# Others.net
KiCad netlist of a schematic drawn in Altium Designer
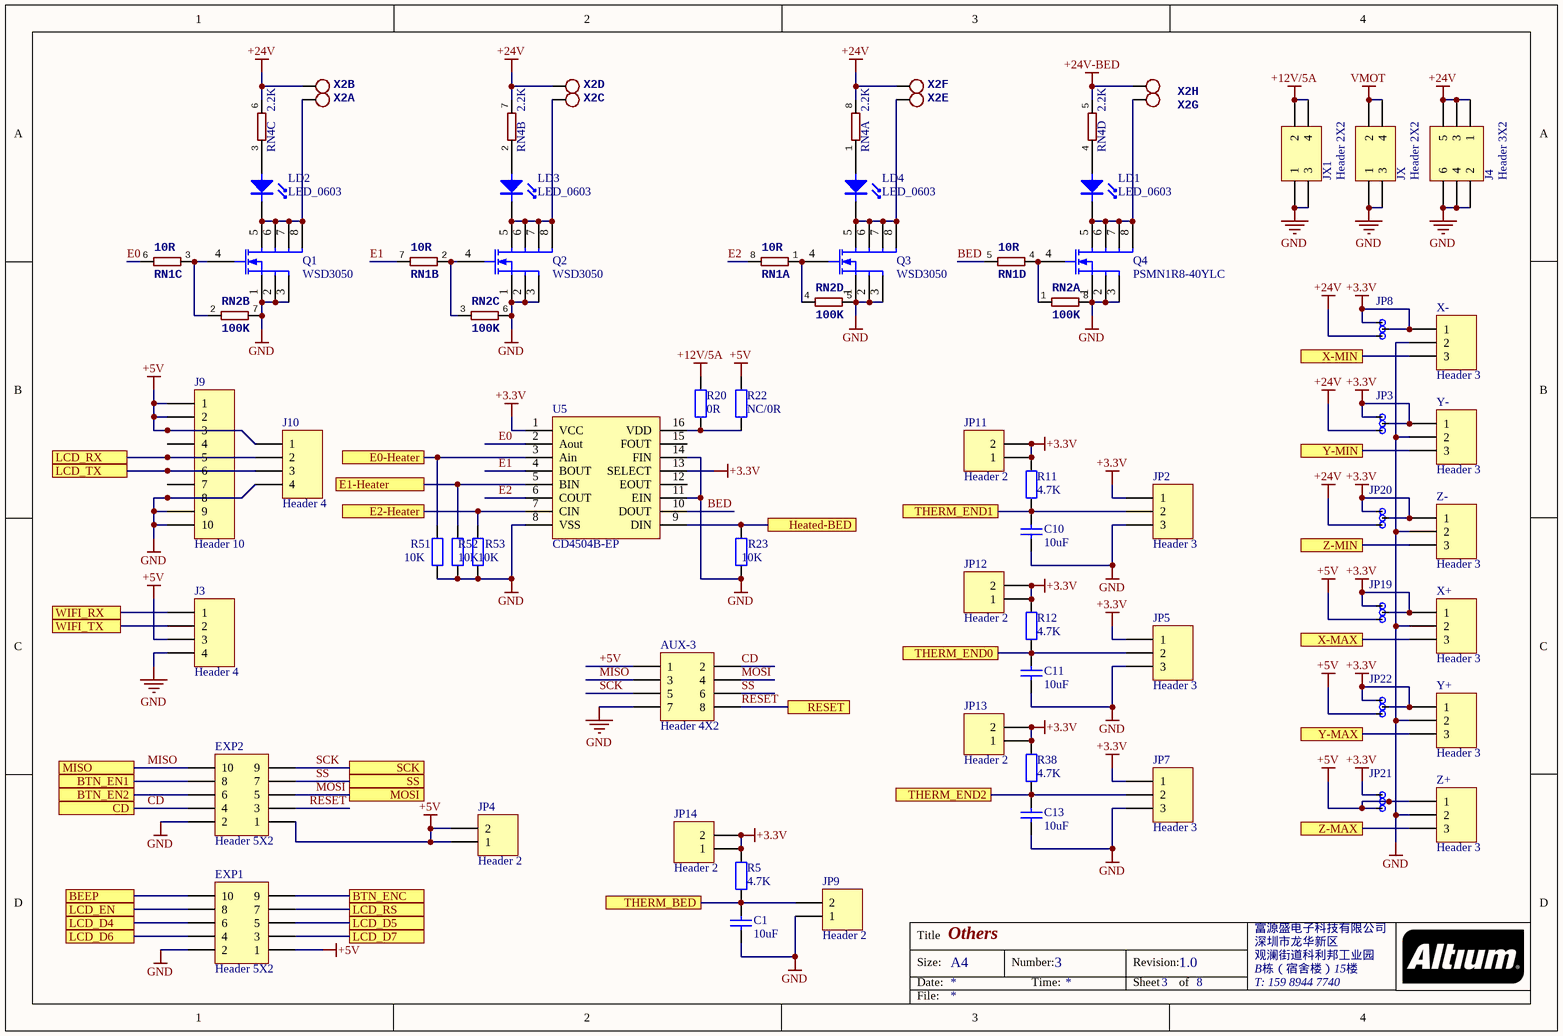
[diagram p0: Others.SchDoc]

(export (version "E")
  (design (tool "Eeschema 10.0.6"))
  (components
    (comp (ref "AUX-3")
      (value "Header 4X2")
      (footprint "Header 2X4")
      (description "Header, 4-Pin, Dual row")
      (fields (field (name "PUBLISHER") "Altium Limited"))
      (libsource (lib "Miscellaneous Connectors") (part "Header 4X2"))
    )
    (comp (ref "C1")
      (value "10uF")
      (footprint "CAP0805")
      (description "RO C0G 22pF 2% 50V  0603")
      (libsource (lib "Ultimaker") (part "Capacitor"))
    )
    (comp (ref "C10")
      (value "10uF")
      (footprint "CAP0805")
      (description "RO C0G 22pF 2% 50V  0603")
      (libsource (lib "Ultimaker") (part "Capacitor"))
    )
    (comp (ref "C11")
      (value "10uF")
      (footprint "CAP0805")
      (description "RO C0G 22pF 2% 50V  0603")
      (libsource (lib "Ultimaker") (part "Capacitor"))
    )
    (comp (ref "C13")
      (value "10uF")
      (footprint "CAP0805")
      (description "RO C0G 22pF 2% 50V  0603")
      (libsource (lib "Ultimaker") (part "Capacitor"))
    )
    (comp (ref "EXP1")
      (value "Header 5X2")
      (footprint "CON-ML_ML10")
      (description "Header, 5-Pin, Dual row")
      (fields (field (name "PUBLISHER") "Altium Limited"))
      (libsource (lib "Miscellaneous Connectors") (part "Header 5X2"))
    )
    (comp (ref "EXP2")
      (value "Header 5X2")
      (footprint "CON-ML_ML10")
      (description "Header, 5-Pin, Dual row")
      (fields (field (name "PUBLISHER") "Altium Limited"))
      (libsource (lib "Miscellaneous Connectors") (part "Header 5X2"))
    )
    (comp (ref "J3")
      (value "Header 4")
      (footprint "1x4 MTE Straight Header 2.54mm")
      (description "Header, 4-Pin")
      (fields (field (name "PUBLISHER") "Altium Limited"))
      (libsource (lib "Miscellaneous Connectors") (part "Header 4"))
    )
    (comp (ref "J4")
      (value "Header 3X2")
      (footprint "header 2X3")
      (description "Header, 3-Pin, Dual row")
      (fields (field (name "PUBLISHER") "Altium Limited"))
      (libsource (lib "Miscellaneous Connectors") (part "Header 3X2"))
    )
    (comp (ref "J9")
      (value "Header 10")
      (footprint "1.0mm_掀盖FPC")
      (description "Header, 10-Pin")
      (fields (field (name "PUBLISHER") "Altium Limited"))
      (libsource (lib "Miscellaneous Connectors") (part "Header 10"))
    )
    (comp (ref "J10")
      (value "Header 4")
      (footprint "Header 1X4")
      (description "Header, 4-Pin")
      (fields (field (name "PUBLISHER") "Altium Limited"))
      (libsource (lib "Miscellaneous Connectors") (part "Header 4"))
    )
    (comp (ref "JP2")
      (value "Header 3")
      (footprint "1X3 MTE STRAIGHT HEADER 2.54MM")
      (description "Header, 3-Pin")
      (fields (field (name "PUBLISHER") "Altium Limited"))
      (libsource (lib "Miscellaneous Connectors") (part "Header 3"))
    )
    (comp (ref "JP3")
      (value "Jumper-3P")
      (footprint "PAD-JUMPER-3-2OF3_NC_BY_PASTE_YES_SILK_FULL_BOX")
      (libsource (lib "接插件库") (part "Jumper-3P"))
    )
    (comp (ref "JP4")
      (value "Header 2")
      (footprint "Jumper2")
      (description "Header, 2-Pin")
      (fields (field (name "PUBLISHER") "Altium Limited"))
      (libsource (lib "Miscellaneous Connectors") (part "Header 2"))
    )
    (comp (ref "JP5")
      (value "Header 3")
      (footprint "1X3 MTE STRAIGHT HEADER 2.54MM")
      (description "Header, 3-Pin")
      (fields (field (name "PUBLISHER") "Altium Limited"))
      (libsource (lib "Miscellaneous Connectors") (part "Header 3"))
    )
    (comp (ref "JP7")
      (value "Header 3")
      (footprint "1X3 MTE STRAIGHT HEADER 2.54MM")
      (description "Header, 3-Pin")
      (fields (field (name "PUBLISHER") "Altium Limited"))
      (libsource (lib "Miscellaneous Connectors") (part "Header 3"))
    )
    (comp (ref "JP8")
      (value "Jumper-3P")
      (footprint "PAD-JUMPER-3-2OF3_NC_BY_PASTE_YES_SILK_FULL_BOX")
      (libsource (lib "接插件库") (part "Jumper-3P"))
    )
    (comp (ref "JP9")
      (value "Header 2")
      (footprint "1X2 MTE STRAIGHT HEADER 2.54MM")
      (description "Header, 2-Pin")
      (fields (field (name "PUBLISHER") "Altium Limited"))
      (libsource (lib "Miscellaneous Connectors") (part "Header 2"))
    )
    (comp (ref "JP11")
      (value "Header 2")
      (footprint "Jumper2")
      (description "Header, 2-Pin")
      (fields (field (name "PUBLISHER") "Altium Limited"))
      (libsource (lib "") (part "Header 2_1"))
    )
    (comp (ref "JP12")
      (value "Header 2")
      (footprint "Jumper2")
      (description "Header, 2-Pin")
      (fields (field (name "PUBLISHER") "Altium Limited"))
      (libsource (lib "") (part "Header 2_1"))
    )
    (comp (ref "JP13")
      (value "Header 2")
      (footprint "Jumper2")
      (description "Header, 2-Pin")
      (fields (field (name "PUBLISHER") "Altium Limited"))
      (libsource (lib "") (part "Header 2_1"))
    )
    (comp (ref "JP14")
      (value "Header 2")
      (footprint "Jumper2")
      (description "Header, 2-Pin")
      (fields (field (name "PUBLISHER") "Altium Limited"))
      (libsource (lib "") (part "Header 2_1"))
    )
    (comp (ref "JP19")
      (value "Jumper-3P")
      (footprint "PAD-JUMPER-3-2OF3_NC_BY_PASTE_YES_SILK_FULL_BOX")
      (libsource (lib "接插件库") (part "Jumper-3P"))
    )
    (comp (ref "JP20")
      (value "Jumper-3P")
      (footprint "PAD-JUMPER-3-2OF3_NC_BY_PASTE_YES_SILK_FULL_BOX")
      (libsource (lib "接插件库") (part "Jumper-3P"))
    )
    (comp (ref "JP21")
      (value "Jumper-3P")
      (footprint "PAD-JUMPER-3-2OF3_NC_BY_PASTE_YES_SILK_FULL_BOX")
      (libsource (lib "接插件库") (part "Jumper-3P"))
    )
    (comp (ref "JP22")
      (value "Jumper-3P")
      (footprint "PAD-JUMPER-3-2OF3_NC_BY_PASTE_YES_SILK_FULL_BOX")
      (libsource (lib "接插件库") (part "Jumper-3P"))
    )
    (comp (ref "JX")
      (value "Header 2X2")
      (footprint "Header 2X2")
      (description "Header, 2-Pin, Dual row")
      (fields (field (name "PUBLISHER") "Altium Limited"))
      (libsource (lib "Miscellaneous Connectors") (part "Header 2X2"))
    )
    (comp (ref "JX1")
      (value "Header 2X2")
      (footprint "Header 2X2")
      (description "Header, 2-Pin, Dual row")
      (fields (field (name "PUBLISHER") "Altium Limited"))
      (libsource (lib "Miscellaneous Connectors") (part "Header 2X2"))
    )
    (comp (ref "LD1") (value "LED_0603") (footprint "LED0603") (libsource (lib "接插件库") (part "LED_0603")))
    (comp (ref "LD2") (value "LED_0603") (footprint "LED0603") (libsource (lib "接插件库") (part "LED_0603")))
    (comp (ref "LD3") (value "LED_0603") (footprint "LED0603") (libsource (lib "接插件库") (part "LED_0603")))
    (comp (ref "LD4") (value "LED_0603") (footprint "LED0603") (libsource (lib "接插件库") (part "LED_0603")))
    (comp (ref "Q1")
      (value "WSD3050")
      (footprint "DFN3X3-8L")
      (description "IRF8736PBF - MOSFET, N SO-8")
      (fields (field (name "MFG") "INTERNATIONAL RECTIFIER"))
      (libsource (lib "Ultimaker2") (part "MOSFET-N-SO8"))
    )
    (comp (ref "Q2")
      (value "WSD3050")
      (footprint "DFN3X3-8L")
      (description "IRF8736PBF - MOSFET, N SO-8")
      (fields (field (name "MFG") "INTERNATIONAL RECTIFIER"))
      (libsource (lib "Ultimaker2") (part "MOSFET-N-SO8"))
    )
    (comp (ref "Q3")
      (value "WSD3050")
      (footprint "DFN3X3-8L")
      (description "IRF8736PBF - MOSFET, N SO-8")
      (fields (field (name "MFG") "INTERNATIONAL RECTIFIER"))
      (libsource (lib "Ultimaker2") (part "MOSFET-N-SO8"))
    )
    (comp (ref "Q4")
      (value "PSMN1R8-40YLC")
      (footprint "NXP_LFPAK56")
      (description "IRF8736PBF - MOSFET, N SO-8")
      (fields (field (name "MFG") "INTERNATIONAL RECTIFIER"))
      (libsource (lib "Ultimaker2") (part "MOSFET-N-SO8"))
    )
    (comp (ref "R5")
      (value "4.7K")
      (footprint "RES0603")
      (description "RO RES 10k0 1% 0,063W  0603")
      (libsource (lib "Ultimaker") (part "Resistor"))
    )
    (comp (ref "R11")
      (value "4.7K")
      (footprint "RES0603")
      (description "RO RES 10k0 1% 0,063W  0603")
      (libsource (lib "Ultimaker") (part "Resistor"))
    )
    (comp (ref "R12")
      (value "4.7K")
      (footprint "RES0603")
      (description "RO RES 10k0 1% 0,063W  0603")
      (libsource (lib "Ultimaker") (part "Resistor"))
    )
    (comp (ref "R20")
      (value "0R")
      (footprint "RES0603")
      (description "RO RES 10k0 1% 0,063W  0603")
      (libsource (lib "") (part "Resistor_1"))
    )
    (comp (ref "R22")
      (value "NC/0R")
      (footprint "RES0603")
      (description "RO RES 10k0 1% 0,063W  0603")
      (libsource (lib "") (part "Resistor_1"))
    )
    (comp (ref "R23")
      (value "10K")
      (footprint "RES0603")
      (description "RO RES 10k0 1% 0,063W  0603")
      (libsource (lib "") (part "Resistor_1"))
    )
    (comp (ref "R38")
      (value "4.7K")
      (footprint "RES0603")
      (description "RO RES 10k0 1% 0,063W  0603")
      (libsource (lib "Ultimaker") (part "Resistor"))
    )
    (comp (ref "R51")
      (value "10K")
      (footprint "RES0603")
      (description "RO RES 10k0 1% 0,063W  0603")
      (libsource (lib "") (part "Resistor_1"))
    )
    (comp (ref "R52")
      (value "10K")
      (footprint "RES0603")
      (description "RO RES 10k0 1% 0,063W  0603")
      (libsource (lib "") (part "Resistor_1"))
    )
    (comp (ref "R53")
      (value "10K")
      (footprint "RES0603")
      (description "RO RES 10k0 1% 0,063W  0603")
      (libsource (lib "") (part "Resistor_1"))
    )
    (comp (ref "RN1")
      (value "10R")
      (footprint "RESISTOR-DIL_CAY16")
      (libsource (lib "接插件库") (part "RESISTOR-DIL_4R-NCAT16"))
    )
    (comp (ref "RN2")
      (value "100K")
      (footprint "RESISTOR-DIL_CAY16")
      (libsource (lib "接插件库") (part "RESISTOR-DIL_4R-NCAT16"))
    )
    (comp (ref "RN4")
      (value "2.2K")
      (footprint "RESISTOR-DIL_CAY16")
      (libsource (lib "接插件库") (part "RESISTOR-DIL_4R-NCAT16"))
    )
    (comp (ref "U5") (value "CD4504B-EP") (footprint "SSOP16") (libsource (lib "接插件库") (part "CD4504B-EP")))
    (comp (ref "X+")
      (value "Header 3")
      (footprint "1x3 MTE Straight Header 2.54mm")
      (description "Header, 3-Pin")
      (fields (field (name "PUBLISHER") "Altium Limited"))
      (libsource (lib "Miscellaneous Connectors") (part "Header 3"))
    )
    (comp (ref "X-")
      (value "Header 3")
      (footprint "1x3 MTE Straight Header 2.54mm")
      (description "Header, 3-Pin")
      (fields (field (name "PUBLISHER") "Altium Limited"))
      (libsource (lib "Miscellaneous Connectors") (part "Header 3"))
    )
    (comp (ref "X2")
      (value "5.08-12P")
      (footprint "CON-PHOENIX-508_MKDSN1,5/12-5,08")
      (fields (field (name "MPN") "SMKDSN1,5/10-5,08"))
      (libsource (lib "接插件库") (part "CON-PHOENIX-508_MKDSN1,5/12-5,08"))
    )
    (comp (ref "Y+")
      (value "Header 3")
      (footprint "1x3 MTE Straight Header 2.54mm")
      (description "Header, 3-Pin")
      (fields (field (name "PUBLISHER") "Altium Limited"))
      (libsource (lib "Miscellaneous Connectors") (part "Header 3"))
    )
    (comp (ref "Y-")
      (value "Header 3")
      (footprint "1x3 MTE Straight Header 2.54mm")
      (description "Header, 3-Pin")
      (fields (field (name "PUBLISHER") "Altium Limited"))
      (libsource (lib "Miscellaneous Connectors") (part "Header 3"))
    )
    (comp (ref "Z+")
      (value "Header 3")
      (footprint "1x3 MTE Straight Header 2.54mm")
      (description "Header, 3-Pin")
      (fields (field (name "PUBLISHER") "Altium Limited"))
      (libsource (lib "Miscellaneous Connectors") (part "Header 3"))
    )
    (comp (ref "Z-")
      (value "Header 3")
      (footprint "1x3 MTE Straight Header 2.54mm")
      (description "Header, 3-Pin")
      (fields (field (name "PUBLISHER") "Altium Limited"))
      (libsource (lib "Miscellaneous Connectors") (part "Header 3"))
    )
  )
  (nets
    (net (code "1") (name "+3.3V") (class "Default")
      (node (ref "JP11") (pin "1") (pinfunction "1_1") (pintype "passive"))
      (node (ref "JP11") (pin "2") (pinfunction "2_2") (pintype "passive"))
      (node (ref "JP12") (pin "1") (pinfunction "1_1") (pintype "passive"))
      (node (ref "JP12") (pin "2") (pinfunction "2_2") (pintype "passive"))
      (node (ref "JP13") (pin "1") (pinfunction "1_1") (pintype "passive"))
      (node (ref "JP13") (pin "2") (pinfunction "2_2") (pintype "passive"))
      (node (ref "JP14") (pin "1") (pinfunction "1_1") (pintype "passive"))
      (node (ref "JP14") (pin "2") (pinfunction "2_2") (pintype "passive"))
      (node (ref "JP19") (pin "1") (pintype "passive"))
      (node (ref "JP19") (pin "2") (pintype "passive"))
      (node (ref "JP2") (pin "1") (pinfunction "1_1") (pintype "passive"))
      (node (ref "JP20") (pin "1") (pintype "passive"))
      (node (ref "JP20") (pin "2") (pintype "passive"))
      (node (ref "JP21") (pin "1") (pintype "passive"))
      (node (ref "JP22") (pin "1") (pintype "passive"))
      (node (ref "JP22") (pin "2") (pintype "passive"))
      (node (ref "JP3") (pin "1") (pintype "passive"))
      (node (ref "JP3") (pin "2") (pintype "passive"))
      (node (ref "JP5") (pin "1") (pinfunction "1_1") (pintype "passive"))
      (node (ref "JP7") (pin "1") (pinfunction "1_1") (pintype "passive"))
      (node (ref "JP8") (pin "1") (pintype "passive"))
      (node (ref "JP8") (pin "2") (pintype "passive"))
      (node (ref "R11") (pin "2") (pinfunction "2_2") (pintype "passive"))
      (node (ref "R12") (pin "2") (pinfunction "2_2") (pintype "passive"))
      (node (ref "R38") (pin "2") (pinfunction "2_2") (pintype "passive"))
      (node (ref "R5") (pin "2") (pinfunction "2_2") (pintype "passive"))
      (node (ref "U5") (pin "1") (pinfunction "VCC_1") (pintype "passive"))
      (node (ref "U5") (pin "13") (pinfunction "SELECT_13") (pintype "passive"))
      (node (ref "X+") (pin "1") (pinfunction "1_1") (pintype "passive"))
      (node (ref "X-") (pin "1") (pinfunction "1_1") (pintype "passive"))
      (node (ref "Y+") (pin "1") (pinfunction "1_1") (pintype "passive"))
      (node (ref "Y-") (pin "1") (pinfunction "1_1") (pintype "passive"))
      (node (ref "Z-") (pin "1") (pinfunction "1_1") (pintype "passive"))
    )
    (net (code "2") (name "+5V") (class "Default")
      (node (ref "AUX-3") (pin "1") (pinfunction "1_1") (pintype "passive"))
      (node (ref "EXP1") (pin "1") (pinfunction "1_1") (pintype "passive"))
      (node (ref "EXP2") (pin "1") (pinfunction "1_1") (pintype "passive"))
      (node (ref "J10") (pin "1") (pinfunction "1_1") (pintype "passive"))
      (node (ref "J3") (pin "3") (pinfunction "3_3") (pintype "passive"))
      (node (ref "J9") (pin "1") (pinfunction "1_1") (pintype "passive"))
      (node (ref "J9") (pin "2") (pinfunction "2_2") (pintype "passive"))
      (node (ref "J9") (pin "3") (pinfunction "3_3") (pintype "passive"))
      (node (ref "JP19") (pin "3") (pintype "passive"))
      (node (ref "JP21") (pin "2") (pintype "passive"))
      (node (ref "JP21") (pin "3") (pintype "passive"))
      (node (ref "JP22") (pin "3") (pintype "passive"))
      (node (ref "JP4") (pin "1") (pinfunction "1_1") (pintype "passive"))
      (node (ref "JP4") (pin "2") (pinfunction "2_2") (pintype "passive"))
      (node (ref "R22") (pin "1") (pinfunction "1_1") (pintype "passive"))
      (node (ref "Z+") (pin "1") (pinfunction "1_1") (pintype "passive"))
    )
    (net (code "3") (name "+12V{slash}5A") (class "Default")
      (node (ref "JX1") (pin "2") (pinfunction "2_2") (pintype "passive"))
      (node (ref "JX1") (pin "4") (pinfunction "4_4") (pintype "passive"))
      (node (ref "R20") (pin "1") (pinfunction "1_1") (pintype "passive"))
    )
    (net (code "4") (name "+24V") (class "Default")
      (node (ref "J4") (pin "1") (pinfunction "1_1") (pintype "passive"))
      (node (ref "J4") (pin "3") (pinfunction "3_3") (pintype "passive"))
      (node (ref "J4") (pin "5") (pinfunction "5_5") (pintype "passive"))
      (node (ref "JP20") (pin "3") (pintype "passive"))
      (node (ref "JP3") (pin "3") (pintype "passive"))
      (node (ref "JP8") (pin "3") (pintype "passive"))
      (node (ref "RN4") (pin "6") (pinfunction "2_6") (pintype "passive"))
      (node (ref "RN4") (pin "7") (pinfunction "2_7") (pintype "passive"))
      (node (ref "RN4") (pin "8") (pinfunction "2_8") (pintype "passive"))
      (node (ref "X2") (pin "2") (pinfunction "KL_2") (pintype "passive"))
      (node (ref "X2") (pin "4") (pinfunction "KL_4") (pintype "passive"))
      (node (ref "X2") (pin "6") (pinfunction "KL_6") (pintype "passive"))
    )
    (net (code "5") (name "+24V-BED") (class "Default")
      (node (ref "RN4") (pin "5") (pinfunction "2_5") (pintype "passive"))
      (node (ref "X2") (pin "8") (pinfunction "KL_8") (pintype "passive"))
    )
    (net (code "6") (name "/BED") (class "Default")
      (node (ref "RN1") (pin "5") (pinfunction "2_5") (pintype "passive"))
      (node (ref "U5") (pin "10") (pinfunction "DOUT_10") (pintype "passive"))
    )
    (net (code "7") (name "/BEEP") (class "Default")
      (node (ref "EXP1") (pin "10") (pinfunction "10_10") (pintype "passive"))
    )
    (net (code "8") (name "/BTN_EN1") (class "Default")
      (node (ref "EXP2") (pin "8") (pinfunction "8_8") (pintype "passive"))
    )
    (net (code "9") (name "/BTN_EN2") (class "Default")
      (node (ref "EXP2") (pin "6") (pinfunction "6_6") (pintype "passive"))
    )
    (net (code "10") (name "/BTN_ENC") (class "Default")
      (node (ref "EXP1") (pin "9") (pinfunction "9_9") (pintype "passive"))
    )
    (net (code "11") (name "/CD") (class "Default")
      (node (ref "AUX-3") (pin "2") (pinfunction "2_2") (pintype "passive"))
      (node (ref "EXP2") (pin "4") (pinfunction "4_4") (pintype "passive"))
    )
    (net (code "12") (name "/E0") (class "Default")
      (node (ref "RN1") (pin "6") (pinfunction "2_6") (pintype "passive"))
      (node (ref "U5") (pin "2") (pinfunction "Aout_2") (pintype "passive"))
    )
    (net (code "13") (name "/E0-Heater") (class "Default")
      (node (ref "R51") (pin "1") (pinfunction "1_1") (pintype "passive"))
      (node (ref "U5") (pin "3") (pinfunction "Ain_3") (pintype "passive"))
    )
    (net (code "14") (name "/E1") (class "Default")
      (node (ref "RN1") (pin "7") (pinfunction "2_7") (pintype "passive"))
      (node (ref "U5") (pin "4") (pinfunction "BOUT_4") (pintype "passive"))
    )
    (net (code "15") (name "/E1-Heater") (class "Default")
      (node (ref "R52") (pin "1") (pinfunction "1_1") (pintype "passive"))
      (node (ref "U5") (pin "5") (pinfunction "BIN_5") (pintype "passive"))
    )
    (net (code "16") (name "/E2") (class "Default")
      (node (ref "RN1") (pin "8") (pinfunction "2_8") (pintype "passive"))
      (node (ref "U5") (pin "6") (pinfunction "COUT_6") (pintype "passive"))
    )
    (net (code "17") (name "/E2-Heater") (class "Default")
      (node (ref "R53") (pin "1") (pinfunction "1_1") (pintype "passive"))
      (node (ref "U5") (pin "7") (pinfunction "CIN_7") (pintype "passive"))
    )
    (net (code "18") (name "/Heated-BED") (class "Default")
      (node (ref "R23") (pin "1") (pinfunction "1_1") (pintype "passive"))
      (node (ref "U5") (pin "9") (pinfunction "DIN_9") (pintype "passive"))
    )
    (net (code "19") (name "/LCD_D4") (class "Default")
      (node (ref "EXP1") (pin "6") (pinfunction "6_6") (pintype "passive"))
    )
    (net (code "20") (name "/LCD_D5") (class "Default")
      (node (ref "EXP1") (pin "5") (pinfunction "5_5") (pintype "passive"))
    )
    (net (code "21") (name "/LCD_D6") (class "Default")
      (node (ref "EXP1") (pin "4") (pinfunction "4_4") (pintype "passive"))
    )
    (net (code "22") (name "/LCD_D7") (class "Default")
      (node (ref "EXP1") (pin "3") (pinfunction "3_3") (pintype "passive"))
    )
    (net (code "23") (name "/LCD_EN") (class "Default")
      (node (ref "EXP1") (pin "8") (pinfunction "8_8") (pintype "passive"))
    )
    (net (code "24") (name "/LCD_RS") (class "Default")
      (node (ref "EXP1") (pin "7") (pinfunction "7_7") (pintype "passive"))
    )
    (net (code "25") (name "/LCD_RX") (class "Default")
      (node (ref "J10") (pin "2") (pinfunction "2_2") (pintype "passive"))
      (node (ref "J9") (pin "5") (pinfunction "5_5") (pintype "passive"))
    )
    (net (code "26") (name "/LCD_TX") (class "Default")
      (node (ref "J10") (pin "3") (pinfunction "3_3") (pintype "passive"))
      (node (ref "J9") (pin "6") (pinfunction "6_6") (pintype "passive"))
    )
    (net (code "27") (name "/MISO") (class "Default")
      (node (ref "AUX-3") (pin "3") (pinfunction "3_3") (pintype "passive"))
      (node (ref "EXP2") (pin "10") (pinfunction "10_10") (pintype "passive"))
    )
    (net (code "28") (name "/MOSI") (class "Default")
      (node (ref "AUX-3") (pin "4") (pinfunction "4_4") (pintype "passive"))
      (node (ref "EXP2") (pin "5") (pinfunction "5_5") (pintype "passive"))
    )
    (net (code "29") (name "/RESET") (class "Default")
      (node (ref "AUX-3") (pin "8") (pinfunction "8_8") (pintype "passive"))
      (node (ref "EXP2") (pin "3") (pinfunction "3_3") (pintype "passive"))
    )
    (net (code "30") (name "/SCK") (class "Default")
      (node (ref "AUX-3") (pin "5") (pinfunction "5_5") (pintype "passive"))
      (node (ref "EXP2") (pin "9") (pinfunction "9_9") (pintype "passive"))
    )
    (net (code "31") (name "/SS") (class "Default")
      (node (ref "AUX-3") (pin "6") (pinfunction "6_6") (pintype "passive"))
      (node (ref "EXP2") (pin "7") (pinfunction "7_7") (pintype "passive"))
    )
    (net (code "32") (name "/THERM_BED") (class "Default")
      (node (ref "C1") (pin "2") (pinfunction "2_2") (pintype "passive"))
      (node (ref "JP9") (pin "2") (pinfunction "2_2") (pintype "passive"))
      (node (ref "R5") (pin "1") (pinfunction "1_1") (pintype "passive"))
    )
    (net (code "33") (name "/THERM_END0") (class "Default")
      (node (ref "C11") (pin "2") (pinfunction "2_2") (pintype "passive"))
      (node (ref "JP5") (pin "2") (pinfunction "2_2") (pintype "passive"))
      (node (ref "R12") (pin "1") (pinfunction "1_1") (pintype "passive"))
    )
    (net (code "34") (name "/THERM_END1") (class "Default")
      (node (ref "C10") (pin "2") (pinfunction "2_2") (pintype "passive"))
      (node (ref "JP2") (pin "2") (pinfunction "2_2") (pintype "passive"))
      (node (ref "R11") (pin "1") (pinfunction "1_1") (pintype "passive"))
    )
    (net (code "35") (name "/THERM_END2") (class "Default")
      (node (ref "C13") (pin "2") (pinfunction "2_2") (pintype "passive"))
      (node (ref "JP7") (pin "2") (pinfunction "2_2") (pintype "passive"))
      (node (ref "R38") (pin "1") (pinfunction "1_1") (pintype "passive"))
    )
    (net (code "36") (name "/WIFI_RX") (class "Default")
      (node (ref "J3") (pin "1") (pinfunction "1_1") (pintype "passive"))
    )
    (net (code "37") (name "/WIFI_TX") (class "Default")
      (node (ref "J3") (pin "2") (pinfunction "2_2") (pintype "passive"))
    )
    (net (code "38") (name "/X-MAX") (class "Default")
      (node (ref "X+") (pin "3") (pinfunction "3_3") (pintype "passive"))
    )
    (net (code "39") (name "/X-MIN") (class "Default")
      (node (ref "X-") (pin "3") (pinfunction "3_3") (pintype "passive"))
    )
    (net (code "40") (name "/Y-MAX") (class "Default")
      (node (ref "Y+") (pin "3") (pinfunction "3_3") (pintype "passive"))
    )
    (net (code "41") (name "/Y-MIN") (class "Default")
      (node (ref "Y-") (pin "3") (pinfunction "3_3") (pintype "passive"))
    )
    (net (code "42") (name "/Z-MAX") (class "Default")
      (node (ref "Z+") (pin "3") (pinfunction "3_3") (pintype "passive"))
    )
    (net (code "43") (name "/Z-MIN") (class "Default")
      (node (ref "Z-") (pin "3") (pinfunction "3_3") (pintype "passive"))
    )
    (net (code "44") (name "GND") (class "Default")
      (node (ref "AUX-3") (pin "7") (pinfunction "7_7") (pintype "passive"))
      (node (ref "C1") (pin "1") (pinfunction "1_1") (pintype "passive"))
      (node (ref "C10") (pin "1") (pinfunction "1_1") (pintype "passive"))
      (node (ref "C11") (pin "1") (pinfunction "1_1") (pintype "passive"))
      (node (ref "C13") (pin "1") (pinfunction "1_1") (pintype "passive"))
      (node (ref "EXP1") (pin "2") (pinfunction "2_2") (pintype "passive"))
      (node (ref "EXP2") (pin "2") (pinfunction "2_2") (pintype "passive"))
      (node (ref "J10") (pin "4") (pinfunction "4_4") (pintype "passive"))
      (node (ref "J3") (pin "4") (pinfunction "4_4") (pintype "passive"))
      (node (ref "J4") (pin "2") (pinfunction "2_2") (pintype "passive"))
      (node (ref "J4") (pin "4") (pinfunction "4_4") (pintype "passive"))
      (node (ref "J4") (pin "6") (pinfunction "6_6") (pintype "passive"))
      (node (ref "J9") (pin "10") (pinfunction "10_10") (pintype "passive"))
      (node (ref "J9") (pin "8") (pinfunction "8_8") (pintype "passive"))
      (node (ref "J9") (pin "9") (pinfunction "9_9") (pintype "passive"))
      (node (ref "JP2") (pin "3") (pinfunction "3_3") (pintype "passive"))
      (node (ref "JP5") (pin "3") (pinfunction "3_3") (pintype "passive"))
      (node (ref "JP7") (pin "3") (pinfunction "3_3") (pintype "passive"))
      (node (ref "JP9") (pin "1") (pinfunction "1_1") (pintype "passive"))
      (node (ref "JX") (pin "1") (pinfunction "1_1") (pintype "passive"))
      (node (ref "JX") (pin "3") (pinfunction "3_3") (pintype "passive"))
      (node (ref "JX1") (pin "1") (pinfunction "1_1") (pintype "passive"))
      (node (ref "JX1") (pin "3") (pinfunction "3_3") (pintype "passive"))
      (node (ref "Q1") (pin "1") (pinfunction "S_1") (pintype "passive"))
      (node (ref "Q1") (pin "2") (pinfunction "S_2") (pintype "passive"))
      (node (ref "Q1") (pin "3") (pinfunction "S_3") (pintype "passive"))
      (node (ref "Q2") (pin "1") (pinfunction "S_1") (pintype "passive"))
      (node (ref "Q2") (pin "2") (pinfunction "S_2") (pintype "passive"))
      (node (ref "Q2") (pin "3") (pinfunction "S_3") (pintype "passive"))
      (node (ref "Q3") (pin "1") (pinfunction "S_1") (pintype "passive"))
      (node (ref "Q3") (pin "2") (pinfunction "S_2") (pintype "passive"))
      (node (ref "Q3") (pin "3") (pinfunction "S_3") (pintype "passive"))
      (node (ref "Q4") (pin "1") (pinfunction "S_1") (pintype "passive"))
      (node (ref "Q4") (pin "2") (pinfunction "S_2") (pintype "passive"))
      (node (ref "Q4") (pin "3") (pinfunction "S_3") (pintype "passive"))
      (node (ref "R23") (pin "2") (pinfunction "2_2") (pintype "passive"))
      (node (ref "R51") (pin "2") (pinfunction "2_2") (pintype "passive"))
      (node (ref "R52") (pin "2") (pinfunction "2_2") (pintype "passive"))
      (node (ref "R53") (pin "2") (pinfunction "2_2") (pintype "passive"))
      (node (ref "RN2") (pin "5") (pinfunction "2_5") (pintype "passive"))
      (node (ref "RN2") (pin "6") (pinfunction "2_6") (pintype "passive"))
      (node (ref "RN2") (pin "7") (pinfunction "2_7") (pintype "passive"))
      (node (ref "RN2") (pin "8") (pinfunction "2_8") (pintype "passive"))
      (node (ref "U5") (pin "11") (pinfunction "EIN_11") (pintype "passive"))
      (node (ref "U5") (pin "14") (pinfunction "FIN_14") (pintype "passive"))
      (node (ref "U5") (pin "8") (pinfunction "VSS_8") (pintype "passive"))
      (node (ref "X+") (pin "2") (pinfunction "2_2") (pintype "passive"))
      (node (ref "X-") (pin "2") (pinfunction "2_2") (pintype "passive"))
      (node (ref "Y+") (pin "2") (pinfunction "2_2") (pintype "passive"))
      (node (ref "Y-") (pin "2") (pinfunction "2_2") (pintype "passive"))
      (node (ref "Z+") (pin "2") (pinfunction "2_2") (pintype "passive"))
      (node (ref "Z-") (pin "2") (pinfunction "2_2") (pintype "passive"))
    )
    (net (code "45") (name "Net-(LD1-A)") (class "Default")
      (node (ref "LD1") (pin "1") (pinfunction "A_1") (pintype "passive"))
      (node (ref "Q4") (pin "5") (pinfunction "D_5") (pintype "passive"))
      (node (ref "Q4") (pin "6") (pinfunction "D_6") (pintype "passive"))
      (node (ref "Q4") (pin "7") (pinfunction "D_7") (pintype "passive"))
      (node (ref "Q4") (pin "8") (pinfunction "D_8") (pintype "passive"))
      (node (ref "X2") (pin "7") (pinfunction "KL_7") (pintype "passive"))
    )
    (net (code "46") (name "Net-(LD1-K)") (class "Default")
      (node (ref "LD1") (pin "2") (pinfunction "K_2") (pintype "passive"))
      (node (ref "RN4") (pin "4") (pinfunction "1_4") (pintype "passive"))
    )
    (net (code "47") (name "Net-(LD2-A)") (class "Default")
      (node (ref "LD2") (pin "1") (pinfunction "A_1") (pintype "passive"))
      (node (ref "Q1") (pin "5") (pinfunction "D_5") (pintype "passive"))
      (node (ref "Q1") (pin "6") (pinfunction "D_6") (pintype "passive"))
      (node (ref "Q1") (pin "7") (pinfunction "D_7") (pintype "passive"))
      (node (ref "Q1") (pin "8") (pinfunction "D_8") (pintype "passive"))
      (node (ref "X2") (pin "1") (pinfunction "KL_1") (pintype "passive"))
    )
    (net (code "48") (name "Net-(LD2-K)") (class "Default")
      (node (ref "LD2") (pin "2") (pinfunction "K_2") (pintype "passive"))
      (node (ref "RN4") (pin "3") (pinfunction "1_3") (pintype "passive"))
    )
    (net (code "49") (name "Net-(LD3-A)") (class "Default")
      (node (ref "LD3") (pin "1") (pinfunction "A_1") (pintype "passive"))
      (node (ref "Q2") (pin "5") (pinfunction "D_5") (pintype "passive"))
      (node (ref "Q2") (pin "6") (pinfunction "D_6") (pintype "passive"))
      (node (ref "Q2") (pin "7") (pinfunction "D_7") (pintype "passive"))
      (node (ref "Q2") (pin "8") (pinfunction "D_8") (pintype "passive"))
      (node (ref "X2") (pin "3") (pinfunction "KL_3") (pintype "passive"))
    )
    (net (code "50") (name "Net-(LD3-K)") (class "Default")
      (node (ref "LD3") (pin "2") (pinfunction "K_2") (pintype "passive"))
      (node (ref "RN4") (pin "2") (pinfunction "1_2") (pintype "passive"))
    )
    (net (code "51") (name "Net-(LD4-A)") (class "Default")
      (node (ref "LD4") (pin "1") (pinfunction "A_1") (pintype "passive"))
      (node (ref "Q3") (pin "5") (pinfunction "D_5") (pintype "passive"))
      (node (ref "Q3") (pin "6") (pinfunction "D_6") (pintype "passive"))
      (node (ref "Q3") (pin "7") (pinfunction "D_7") (pintype "passive"))
      (node (ref "Q3") (pin "8") (pinfunction "D_8") (pintype "passive"))
      (node (ref "X2") (pin "5") (pinfunction "KL_5") (pintype "passive"))
    )
    (net (code "52") (name "Net-(LD4-K)") (class "Default")
      (node (ref "LD4") (pin "2") (pinfunction "K_2") (pintype "passive"))
      (node (ref "RN4") (pin "1") (pinfunction "1_1") (pintype "passive"))
    )
    (net (code "53") (name "Net-(Q1-G)") (class "Default")
      (node (ref "Q1") (pin "4") (pinfunction "G_4") (pintype "passive"))
      (node (ref "RN1") (pin "3") (pinfunction "1_3") (pintype "passive"))
      (node (ref "RN2") (pin "2") (pinfunction "1_2") (pintype "passive"))
    )
    (net (code "54") (name "Net-(Q2-G)") (class "Default")
      (node (ref "Q2") (pin "4") (pinfunction "G_4") (pintype "passive"))
      (node (ref "RN1") (pin "2") (pinfunction "1_2") (pintype "passive"))
      (node (ref "RN2") (pin "3") (pinfunction "1_3") (pintype "passive"))
    )
    (net (code "55") (name "Net-(Q3-G)") (class "Default")
      (node (ref "Q3") (pin "4") (pinfunction "G_4") (pintype "passive"))
      (node (ref "RN1") (pin "1") (pinfunction "1_1") (pintype "passive"))
      (node (ref "RN2") (pin "4") (pinfunction "1_4") (pintype "passive"))
    )
    (net (code "56") (name "Net-(Q4-G)") (class "Default")
      (node (ref "Q4") (pin "4") (pinfunction "G_4") (pintype "passive"))
      (node (ref "RN1") (pin "4") (pinfunction "1_4") (pintype "passive"))
      (node (ref "RN2") (pin "1") (pinfunction "1_1") (pintype "passive"))
    )
    (net (code "57") (name "Net-(U5-VDD)") (class "Default")
      (node (ref "R20") (pin "2") (pinfunction "2_2") (pintype "passive"))
      (node (ref "R22") (pin "2") (pinfunction "2_2") (pintype "passive"))
      (node (ref "U5") (pin "16") (pinfunction "VDD_16") (pintype "passive"))
    )
    (net (code "58") (name "VMOT") (class "Default")
      (node (ref "JX") (pin "2") (pinfunction "2_2") (pintype "passive"))
      (node (ref "JX") (pin "4") (pinfunction "4_4") (pintype "passive"))
    )
    (net (code "59") (name "unconnected-(J9-Pad4)") (class "Default")
      (node (ref "J9") (pin "4") (pinfunction "4_4") (pintype "passive"))
    )
    (net (code "60") (name "unconnected-(J9-Pad7)") (class "Default")
      (node (ref "J9") (pin "7") (pinfunction "7_7") (pintype "passive"))
    )
    (net (code "61") (name "unconnected-(U5-EOUT-Pad12)") (class "Default")
      (node (ref "U5") (pin "12") (pinfunction "EOUT_12") (pintype "passive"))
    )
    (net (code "62") (name "unconnected-(U5-FOUT-Pad15)") (class "Default")
      (node (ref "U5") (pin "15") (pinfunction "FOUT_15") (pintype "passive"))
    )
  )
)
